# DRIVER.net
KiCad netlist of a schematic drawn in Altium Designer
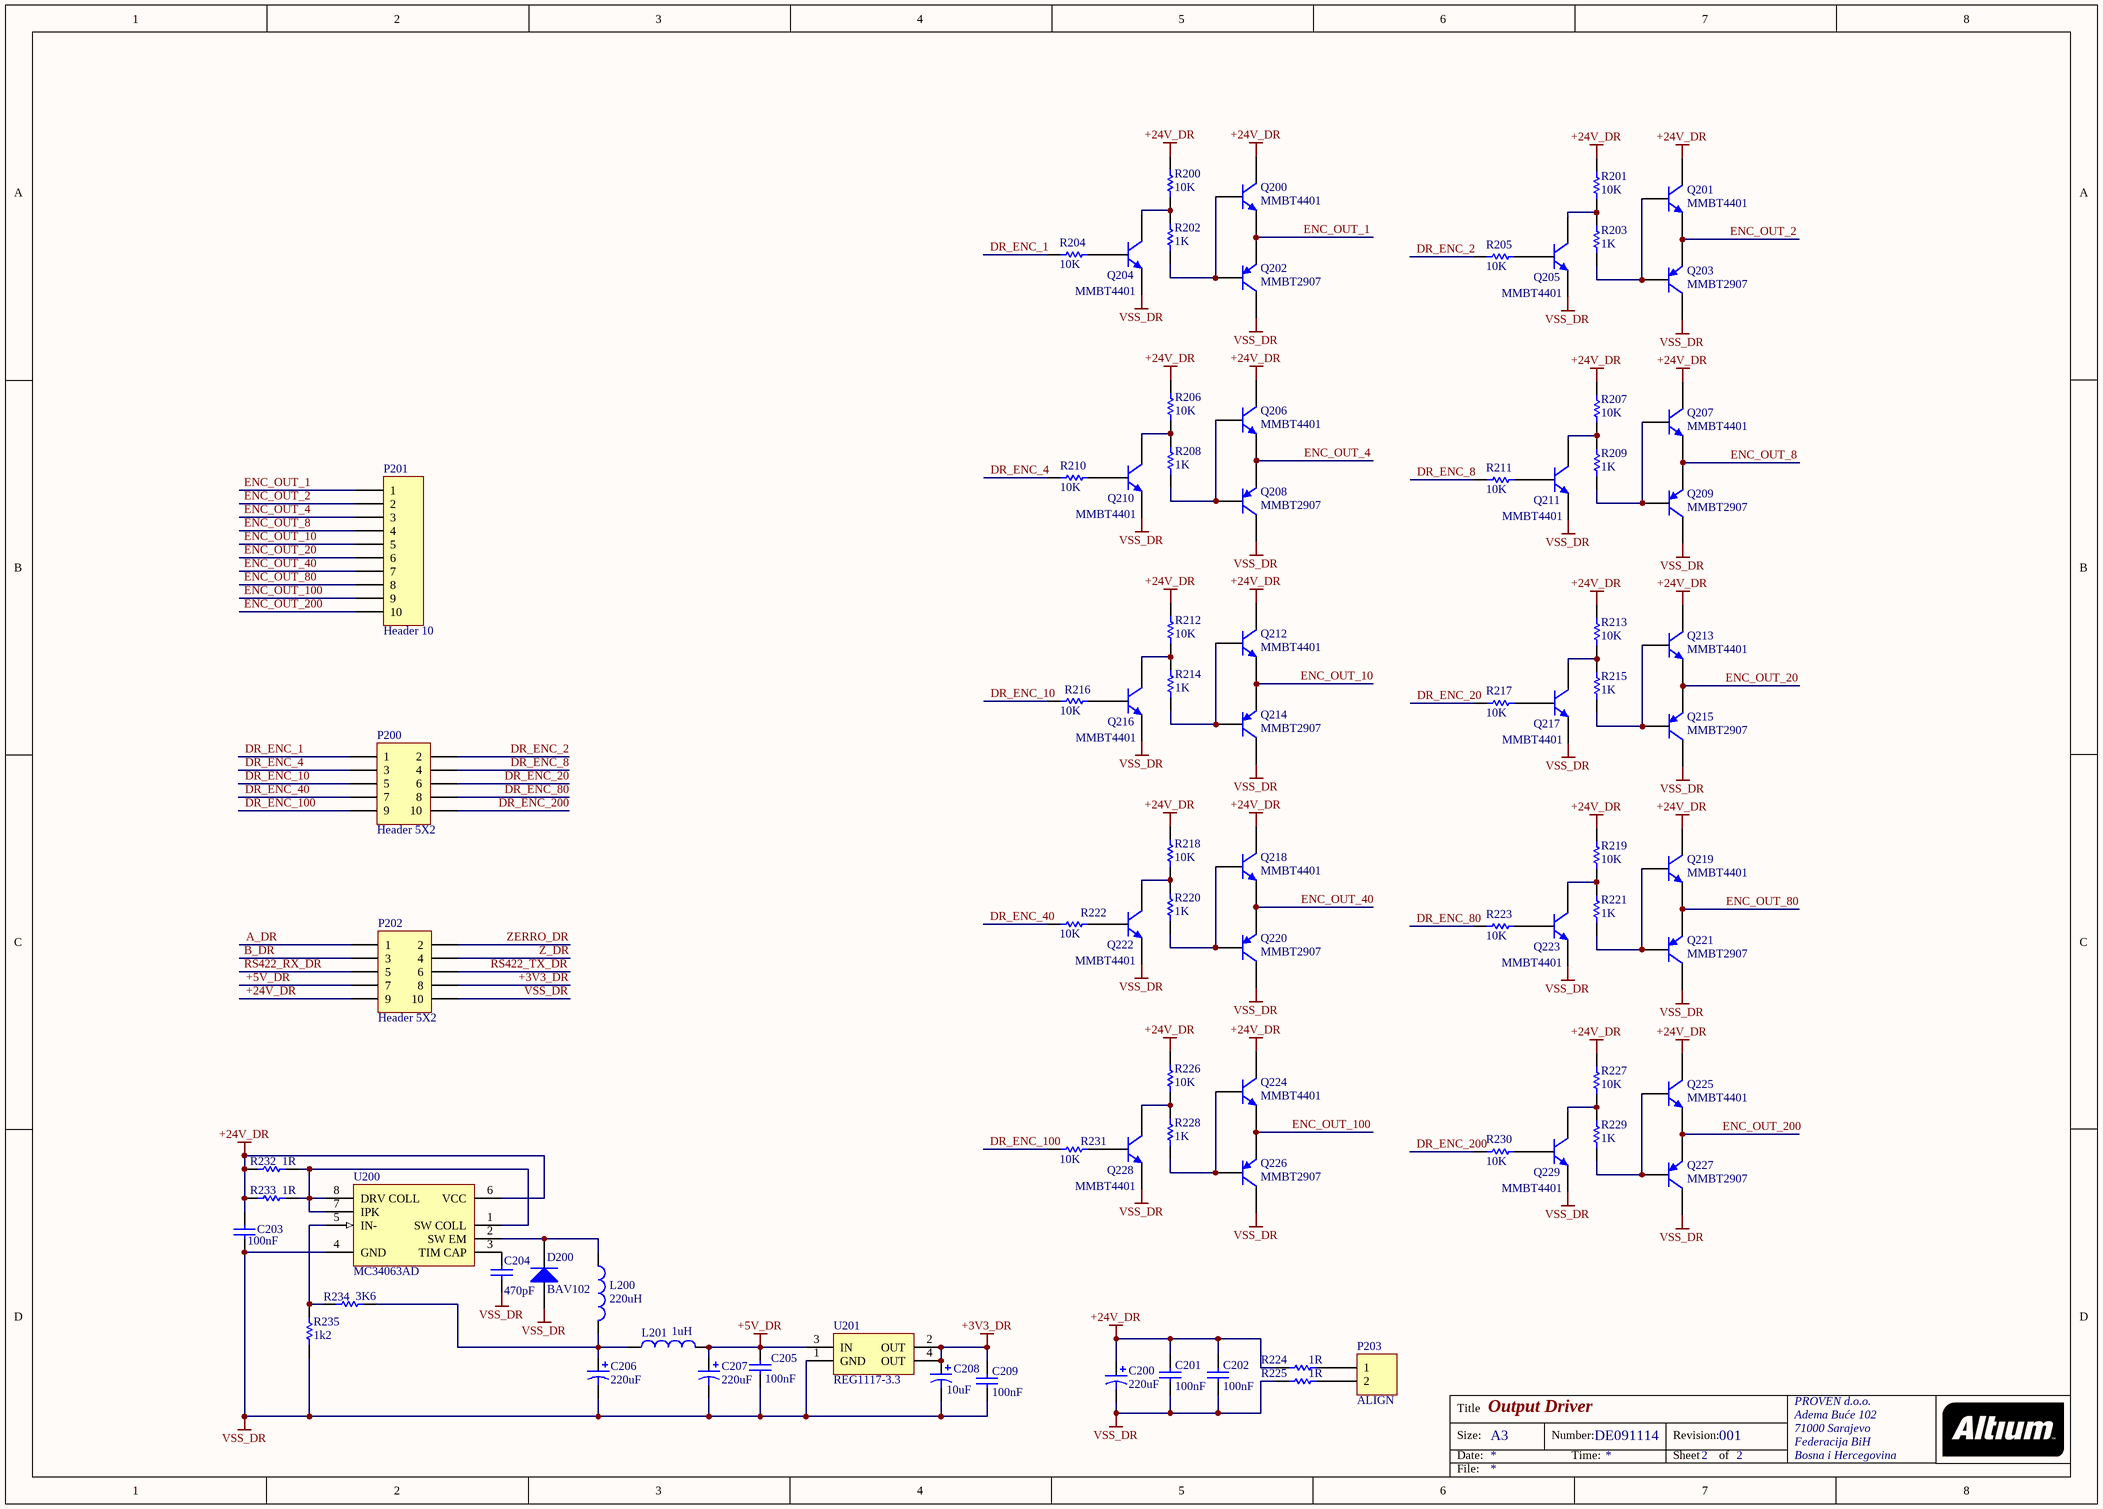
[diagram p0: DRIVER.SchDoc]

(export (version "E")
  (design (tool "Eeschema 10.0.6"))
  (components
    (comp (ref "C200")
      (value "220uF")
      (footprint "E")
      (description "Solid Aluminum Capacitor with Organic Semiconductor Electrolyte: 100uF, 20V, Bulk Pack")
      (fields (field (name "PUBLISHER") "Altium Limited"))
      (libsource (lib "Vishay Electrolytic Radial-Lead Capacitor") (part "94SS107X0020EBP"))
    )
    (comp (ref "C201")
      (value "100nF")
      (footprint "0805")
      (description "Ceramic Chip Capacitor - Standard")
      (fields (field (name "PUBLISHER") "Altium Limited"))
      (libsource (lib "KEMET Chip Capacitor") (part "C0805"))
    )
    (comp (ref "C202")
      (value "100nF")
      (footprint "0805")
      (description "Ceramic Chip Capacitor - Standard")
      (fields (field (name "PUBLISHER") "Altium Limited"))
      (libsource (lib "KEMET Chip Capacitor") (part "C0805"))
    )
    (comp (ref "C203")
      (value "100nF")
      (footprint "1206")
      (description "Ceramic Chip Capacitor - Standard")
      (fields (field (name "PUBLISHER") "Altium Limited"))
      (libsource (lib "KEMET Chip Capacitor") (part "C1206"))
    )
    (comp (ref "C204")
      (value "470pF")
      (footprint "0805")
      (description "Ceramic Chip Capacitor - Standard")
      (fields (field (name "PUBLISHER") "Altium Limited"))
      (libsource (lib "KEMET Chip Capacitor") (part "C0805"))
    )
    (comp (ref "C205")
      (value "100nF")
      (footprint "0805")
      (description "Ceramic Chip Capacitor - Standard")
      (fields (field (name "PUBLISHER") "Altium Limited"))
      (libsource (lib "KEMET Chip Capacitor") (part "C0805"))
    )
    (comp (ref "C206")
      (value "220uF")
      (footprint "CAPPR2-5X11")
      (description "Aluminum Electrolytic Capacitor, Radial Style with Long Leads: 220uF, 10V")
      (fields (field (name "PUBLISHER") "Altium Limited"))
      (libsource (lib "Vishay Roederstein Electrolytic Radial-Lead Capacitor") (part "EKA00AA322C00"))
    )
    (comp (ref "C207")
      (value "220uF")
      (footprint "CAPPR2-5X11")
      (description "Aluminum Electrolytic Capacitor, Radial Style with Long Leads: 220uF, 10V")
      (fields (field (name "PUBLISHER") "Altium Limited"))
      (libsource (lib "Vishay Roederstein Electrolytic Radial-Lead Capacitor") (part "EKA00AA322C00"))
    )
    (comp (ref "C208")
      (value "10uF")
      (footprint "49BC-C")
      (fields (field (name "PUBLISHER") "Altium Limited"))
      (libsource (lib "Vishay Sprague Tantalum Chip Capacitor") (part "49BC685B010M"))
    )
    (comp (ref "C209")
      (value "100nF")
      (footprint "0805")
      (description "Ceramic Chip Capacitor - Standard")
      (fields (field (name "PUBLISHER") "Altium Limited"))
      (libsource (lib "KEMET Chip Capacitor") (part "C0805"))
    )
    (comp (ref "D200")
      (value "BAV102")
      (footprint "SOD80C")
      (description "General-purpose Diode")
      (fields (field (name "PUBLISHER") "Altium Limited"))
      (libsource (lib "Philips Discrete Diode - Switching") (part "BAV102"))
    )
    (comp (ref "L200")
      (value "220uH")
      (footprint "Miscellaneous Devices:RB5-10.5")
      (description "SMT Power Choke Coil; Size 7.3×6.6×3.0mm, ±20% Tolerance, 0.82uH, 13A")
      (fields (field (name "PUBLISHER") "Altium Limited"))
      (libsource (lib "SSM Inductor") (part "PCMC063T-R82MN"))
    )
    (comp (ref "L201")
      (value "1uH")
      (footprint "Miscellaneous Devices:RB5-10.5")
      (description "SMT Power Choke Coil; Size 7.3×6.6×3.0mm, ±20% Tolerance, 0.82uH, 13A")
      (fields (field (name "PUBLISHER") "Altium Limited"))
      (libsource (lib "SSM Inductor") (part "PCMC063T-R82MN"))
    )
    (comp (ref "P200")
      (value "Header 5X2")
      (footprint "HDR2X5")
      (description "Header, 5-Pin, Dual row")
      (fields (field (name "PUBLISHER") "Altium Limited"))
      (libsource (lib "Miscellaneous Connectors") (part "Header 5X2"))
    )
    (comp (ref "P201")
      (value "Header 10")
      (footprint "HDR1X10")
      (description "Header, 10-Pin")
      (fields (field (name "PUBLISHER") "Altium Limited"))
      (libsource (lib "Miscellaneous Connectors") (part "Header 10"))
    )
    (comp (ref "P202")
      (value "Header 5X2")
      (footprint "HDR2X5")
      (description "Header, 5-Pin, Dual row")
      (fields (field (name "PUBLISHER") "Altium Limited"))
      (libsource (lib "Miscellaneous Connectors") (part "Header 5X2"))
    )
    (comp (ref "P203")
      (value "ALIGN")
      (footprint "HDR1X2")
      (description "Header, 2-Pin")
      (fields (field (name "PUBLISHER") "Altium Limited"))
      (libsource (lib "Miscellaneous Connectors") (part "Header 2"))
    )
    (comp (ref "Q200")
      (value "MMBT4401")
      (footprint "SOT23_N")
      (description "NPN General-purpose Transistor")
      (fields (field (name "PUBLISHER") "Altium Limited"))
      (libsource (lib "Philips Discrete BJT - Low Power") (part "BC817-16"))
    )
    (comp (ref "Q201")
      (value "MMBT4401")
      (footprint "SOT23_N")
      (description "NPN General-purpose Transistor")
      (fields (field (name "PUBLISHER") "Altium Limited"))
      (libsource (lib "Philips Discrete BJT - Low Power") (part "BC817-16"))
    )
    (comp (ref "Q202")
      (value "MMBT2907")
      (footprint "SOT23_N")
      (description "PNP General-purpose Transistor")
      (fields (field (name "PUBLISHER") "Altium Limited"))
      (libsource (lib "Philips Discrete BJT - Low Power") (part "BC807-16"))
    )
    (comp (ref "Q203")
      (value "MMBT2907")
      (footprint "SOT23_N")
      (description "PNP General-purpose Transistor")
      (fields (field (name "PUBLISHER") "Altium Limited"))
      (libsource (lib "Philips Discrete BJT - Low Power") (part "BC807-16"))
    )
    (comp (ref "Q204")
      (value "MMBT4401")
      (footprint "SOT23_N")
      (description "NPN General-purpose Transistor")
      (fields (field (name "PUBLISHER") "Altium Limited"))
      (libsource (lib "Philips Discrete BJT - Low Power") (part "BC817-16"))
    )
    (comp (ref "Q205")
      (value "MMBT4401")
      (footprint "SOT23_N")
      (description "NPN General-purpose Transistor")
      (fields (field (name "PUBLISHER") "Altium Limited"))
      (libsource (lib "Philips Discrete BJT - Low Power") (part "BC817-16"))
    )
    (comp (ref "Q206")
      (value "MMBT4401")
      (footprint "SOT23_N")
      (description "NPN General-purpose Transistor")
      (fields (field (name "PUBLISHER") "Altium Limited"))
      (libsource (lib "Philips Discrete BJT - Low Power") (part "BC817-16"))
    )
    (comp (ref "Q207")
      (value "MMBT4401")
      (footprint "SOT23_N")
      (description "NPN General-purpose Transistor")
      (fields (field (name "PUBLISHER") "Altium Limited"))
      (libsource (lib "Philips Discrete BJT - Low Power") (part "BC817-16"))
    )
    (comp (ref "Q208")
      (value "MMBT2907")
      (footprint "SOT23_N")
      (description "PNP General-purpose Transistor")
      (fields (field (name "PUBLISHER") "Altium Limited"))
      (libsource (lib "Philips Discrete BJT - Low Power") (part "BC807-16"))
    )
    (comp (ref "Q209")
      (value "MMBT2907")
      (footprint "SOT23_N")
      (description "PNP General-purpose Transistor")
      (fields (field (name "PUBLISHER") "Altium Limited"))
      (libsource (lib "Philips Discrete BJT - Low Power") (part "BC807-16"))
    )
    (comp (ref "Q210")
      (value "MMBT4401")
      (footprint "SOT23_N")
      (description "NPN General-purpose Transistor")
      (fields (field (name "PUBLISHER") "Altium Limited"))
      (libsource (lib "Philips Discrete BJT - Low Power") (part "BC817-16"))
    )
    (comp (ref "Q211")
      (value "MMBT4401")
      (footprint "SOT23_N")
      (description "NPN General-purpose Transistor")
      (fields (field (name "PUBLISHER") "Altium Limited"))
      (libsource (lib "Philips Discrete BJT - Low Power") (part "BC817-16"))
    )
    (comp (ref "Q212")
      (value "MMBT4401")
      (footprint "SOT23_N")
      (description "NPN General-purpose Transistor")
      (fields (field (name "PUBLISHER") "Altium Limited"))
      (libsource (lib "Philips Discrete BJT - Low Power") (part "BC817-16"))
    )
    (comp (ref "Q213")
      (value "MMBT4401")
      (footprint "SOT23_N")
      (description "NPN General-purpose Transistor")
      (fields (field (name "PUBLISHER") "Altium Limited"))
      (libsource (lib "Philips Discrete BJT - Low Power") (part "BC817-16"))
    )
    (comp (ref "Q214")
      (value "MMBT2907")
      (footprint "SOT23_N")
      (description "PNP General-purpose Transistor")
      (fields (field (name "PUBLISHER") "Altium Limited"))
      (libsource (lib "Philips Discrete BJT - Low Power") (part "BC807-16"))
    )
    (comp (ref "Q215")
      (value "MMBT2907")
      (footprint "SOT23_N")
      (description "PNP General-purpose Transistor")
      (fields (field (name "PUBLISHER") "Altium Limited"))
      (libsource (lib "Philips Discrete BJT - Low Power") (part "BC807-16"))
    )
    (comp (ref "Q216")
      (value "MMBT4401")
      (footprint "SOT23_N")
      (description "NPN General-purpose Transistor")
      (fields (field (name "PUBLISHER") "Altium Limited"))
      (libsource (lib "Philips Discrete BJT - Low Power") (part "BC817-16"))
    )
    (comp (ref "Q217")
      (value "MMBT4401")
      (footprint "SOT23_N")
      (description "NPN General-purpose Transistor")
      (fields (field (name "PUBLISHER") "Altium Limited"))
      (libsource (lib "Philips Discrete BJT - Low Power") (part "BC817-16"))
    )
    (comp (ref "Q218")
      (value "MMBT4401")
      (footprint "SOT23_N")
      (description "NPN General-purpose Transistor")
      (fields (field (name "PUBLISHER") "Altium Limited"))
      (libsource (lib "Philips Discrete BJT - Low Power") (part "BC817-16"))
    )
    (comp (ref "Q219")
      (value "MMBT4401")
      (footprint "SOT23_N")
      (description "NPN General-purpose Transistor")
      (fields (field (name "PUBLISHER") "Altium Limited"))
      (libsource (lib "Philips Discrete BJT - Low Power") (part "BC817-16"))
    )
    (comp (ref "Q220")
      (value "MMBT2907")
      (footprint "SOT23_N")
      (description "PNP General-purpose Transistor")
      (fields (field (name "PUBLISHER") "Altium Limited"))
      (libsource (lib "Philips Discrete BJT - Low Power") (part "BC807-16"))
    )
    (comp (ref "Q221")
      (value "MMBT2907")
      (footprint "SOT23_N")
      (description "PNP General-purpose Transistor")
      (fields (field (name "PUBLISHER") "Altium Limited"))
      (libsource (lib "Philips Discrete BJT - Low Power") (part "BC807-16"))
    )
    (comp (ref "Q222")
      (value "MMBT4401")
      (footprint "SOT23_N")
      (description "NPN General-purpose Transistor")
      (fields (field (name "PUBLISHER") "Altium Limited"))
      (libsource (lib "Philips Discrete BJT - Low Power") (part "BC817-16"))
    )
    (comp (ref "Q223")
      (value "MMBT4401")
      (footprint "SOT23_N")
      (description "NPN General-purpose Transistor")
      (fields (field (name "PUBLISHER") "Altium Limited"))
      (libsource (lib "Philips Discrete BJT - Low Power") (part "BC817-16"))
    )
    (comp (ref "Q224")
      (value "MMBT4401")
      (footprint "SOT23_N")
      (description "NPN General-purpose Transistor")
      (fields (field (name "PUBLISHER") "Altium Limited"))
      (libsource (lib "Philips Discrete BJT - Low Power") (part "BC817-16"))
    )
    (comp (ref "Q225")
      (value "MMBT4401")
      (footprint "SOT23_N")
      (description "NPN General-purpose Transistor")
      (fields (field (name "PUBLISHER") "Altium Limited"))
      (libsource (lib "Philips Discrete BJT - Low Power") (part "BC817-16"))
    )
    (comp (ref "Q226")
      (value "MMBT2907")
      (footprint "SOT23_N")
      (description "PNP General-purpose Transistor")
      (fields (field (name "PUBLISHER") "Altium Limited"))
      (libsource (lib "Philips Discrete BJT - Low Power") (part "BC807-16"))
    )
    (comp (ref "Q227")
      (value "MMBT2907")
      (footprint "SOT23_N")
      (description "PNP General-purpose Transistor")
      (fields (field (name "PUBLISHER") "Altium Limited"))
      (libsource (lib "Philips Discrete BJT - Low Power") (part "BC807-16"))
    )
    (comp (ref "Q228")
      (value "MMBT4401")
      (footprint "SOT23_N")
      (description "NPN General-purpose Transistor")
      (fields (field (name "PUBLISHER") "Altium Limited"))
      (libsource (lib "Philips Discrete BJT - Low Power") (part "BC817-16"))
    )
    (comp (ref "Q229")
      (value "MMBT4401")
      (footprint "SOT23_N")
      (description "NPN General-purpose Transistor")
      (fields (field (name "PUBLISHER") "Altium Limited"))
      (libsource (lib "Philips Discrete BJT - Low Power") (part "BC817-16"))
    )
    (comp (ref "R200")
      (value "10K")
      (footprint "ERA-0603")
      (fields (field (name "PUBLISHER") "Altium Limited"))
      (libsource (lib "Panasonic Resistor") (part "ERAV"))
    )
    (comp (ref "R201")
      (value "10K")
      (footprint "ERA-0603")
      (fields (field (name "PUBLISHER") "Altium Limited"))
      (libsource (lib "Panasonic Resistor") (part "ERAV"))
    )
    (comp (ref "R202")
      (value "1K")
      (footprint "ERA-0603")
      (fields (field (name "PUBLISHER") "Altium Limited"))
      (libsource (lib "Panasonic Resistor") (part "ERAV"))
    )
    (comp (ref "R203")
      (value "1K")
      (footprint "ERA-0603")
      (fields (field (name "PUBLISHER") "Altium Limited"))
      (libsource (lib "Panasonic Resistor") (part "ERAV"))
    )
    (comp (ref "R204")
      (value "10K")
      (footprint "ERA-0603")
      (fields (field (name "PUBLISHER") "Altium Limited"))
      (libsource (lib "Panasonic Resistor") (part "ERAV"))
    )
    (comp (ref "R205")
      (value "10K")
      (footprint "ERA-0603")
      (fields (field (name "PUBLISHER") "Altium Limited"))
      (libsource (lib "Panasonic Resistor") (part "ERAV"))
    )
    (comp (ref "R206")
      (value "10K")
      (footprint "ERA-0603")
      (fields (field (name "PUBLISHER") "Altium Limited"))
      (libsource (lib "Panasonic Resistor") (part "ERAV"))
    )
    (comp (ref "R207")
      (value "10K")
      (footprint "ERA-0603")
      (fields (field (name "PUBLISHER") "Altium Limited"))
      (libsource (lib "Panasonic Resistor") (part "ERAV"))
    )
    (comp (ref "R208")
      (value "1K")
      (footprint "ERA-0603")
      (fields (field (name "PUBLISHER") "Altium Limited"))
      (libsource (lib "Panasonic Resistor") (part "ERAV"))
    )
    (comp (ref "R209")
      (value "1K")
      (footprint "ERA-0603")
      (fields (field (name "PUBLISHER") "Altium Limited"))
      (libsource (lib "Panasonic Resistor") (part "ERAV"))
    )
    (comp (ref "R210")
      (value "10K")
      (footprint "ERA-0603")
      (fields (field (name "PUBLISHER") "Altium Limited"))
      (libsource (lib "Panasonic Resistor") (part "ERAV"))
    )
    (comp (ref "R211")
      (value "10K")
      (footprint "ERA-0603")
      (fields (field (name "PUBLISHER") "Altium Limited"))
      (libsource (lib "Panasonic Resistor") (part "ERAV"))
    )
    (comp (ref "R212")
      (value "10K")
      (footprint "ERA-0603")
      (fields (field (name "PUBLISHER") "Altium Limited"))
      (libsource (lib "Panasonic Resistor") (part "ERAV"))
    )
    (comp (ref "R213")
      (value "10K")
      (footprint "ERA-0603")
      (fields (field (name "PUBLISHER") "Altium Limited"))
      (libsource (lib "Panasonic Resistor") (part "ERAV"))
    )
    (comp (ref "R214")
      (value "1K")
      (footprint "ERA-0603")
      (fields (field (name "PUBLISHER") "Altium Limited"))
      (libsource (lib "Panasonic Resistor") (part "ERAV"))
    )
    (comp (ref "R215")
      (value "1K")
      (footprint "ERA-0603")
      (fields (field (name "PUBLISHER") "Altium Limited"))
      (libsource (lib "Panasonic Resistor") (part "ERAV"))
    )
    (comp (ref "R216")
      (value "10K")
      (footprint "ERA-0603")
      (fields (field (name "PUBLISHER") "Altium Limited"))
      (libsource (lib "Panasonic Resistor") (part "ERAV"))
    )
    (comp (ref "R217")
      (value "10K")
      (footprint "ERA-0603")
      (fields (field (name "PUBLISHER") "Altium Limited"))
      (libsource (lib "Panasonic Resistor") (part "ERAV"))
    )
    (comp (ref "R218")
      (value "10K")
      (footprint "ERA-0603")
      (fields (field (name "PUBLISHER") "Altium Limited"))
      (libsource (lib "Panasonic Resistor") (part "ERAV"))
    )
    (comp (ref "R219")
      (value "10K")
      (footprint "ERA-0603")
      (fields (field (name "PUBLISHER") "Altium Limited"))
      (libsource (lib "Panasonic Resistor") (part "ERAV"))
    )
    (comp (ref "R220")
      (value "1K")
      (footprint "ERA-0603")
      (fields (field (name "PUBLISHER") "Altium Limited"))
      (libsource (lib "Panasonic Resistor") (part "ERAV"))
    )
    (comp (ref "R221")
      (value "1K")
      (footprint "ERA-0603")
      (fields (field (name "PUBLISHER") "Altium Limited"))
      (libsource (lib "Panasonic Resistor") (part "ERAV"))
    )
    (comp (ref "R222")
      (value "10K")
      (footprint "ERA-0603")
      (fields (field (name "PUBLISHER") "Altium Limited"))
      (libsource (lib "Panasonic Resistor") (part "ERAV"))
    )
    (comp (ref "R223")
      (value "10K")
      (footprint "ERA-0603")
      (fields (field (name "PUBLISHER") "Altium Limited"))
      (libsource (lib "Panasonic Resistor") (part "ERAV"))
    )
    (comp (ref "R224")
      (value "1R")
      (footprint "ERA-0603")
      (fields (field (name "PUBLISHER") "Altium Limited"))
      (libsource (lib "Panasonic Resistor") (part "ERAV"))
    )
    (comp (ref "R225")
      (value "1R")
      (footprint "ERA-0603")
      (fields (field (name "PUBLISHER") "Altium Limited"))
      (libsource (lib "Panasonic Resistor") (part "ERAV"))
    )
    (comp (ref "R226")
      (value "10K")
      (footprint "ERA-0603")
      (fields (field (name "PUBLISHER") "Altium Limited"))
      (libsource (lib "Panasonic Resistor") (part "ERAV"))
    )
    (comp (ref "R227")
      (value "10K")
      (footprint "ERA-0603")
      (fields (field (name "PUBLISHER") "Altium Limited"))
      (libsource (lib "Panasonic Resistor") (part "ERAV"))
    )
    (comp (ref "R228")
      (value "1K")
      (footprint "ERA-0603")
      (fields (field (name "PUBLISHER") "Altium Limited"))
      (libsource (lib "Panasonic Resistor") (part "ERAV"))
    )
    (comp (ref "R229")
      (value "1K")
      (footprint "ERA-0603")
      (fields (field (name "PUBLISHER") "Altium Limited"))
      (libsource (lib "Panasonic Resistor") (part "ERAV"))
    )
    (comp (ref "R230")
      (value "10K")
      (footprint "ERA-0603")
      (fields (field (name "PUBLISHER") "Altium Limited"))
      (libsource (lib "Panasonic Resistor") (part "ERAV"))
    )
    (comp (ref "R231")
      (value "10K")
      (footprint "ERA-0603")
      (fields (field (name "PUBLISHER") "Altium Limited"))
      (libsource (lib "Panasonic Resistor") (part "ERAV"))
    )
    (comp (ref "R232")
      (value "1R")
      (footprint "ERA-0805")
      (fields (field (name "PUBLISHER") "Altium Limited"))
      (libsource (lib "Panasonic Resistor") (part "ERAS"))
    )
    (comp (ref "R233")
      (value "1R")
      (footprint "ERA-0805")
      (fields (field (name "PUBLISHER") "Altium Limited"))
      (libsource (lib "Panasonic Resistor") (part "ERAS"))
    )
    (comp (ref "R234")
      (value "3K6")
      (footprint "ERA-0805")
      (fields (field (name "PUBLISHER") "Altium Limited"))
      (libsource (lib "Panasonic Resistor") (part "ERAS"))
    )
    (comp (ref "R235")
      (value "1k2")
      (footprint "ERA-0805")
      (fields (field (name "PUBLISHER") "Altium Limited"))
      (libsource (lib "Panasonic Resistor") (part "ERAS"))
    )
    (comp (ref "U200")
      (value "MC34063AD")
      (footprint "751-05_N")
      (description "DC-to-DC Converter Control Circuit")
      (fields (field (name "PUBLISHER") "Altium Limited"))
      (libsource (lib "ON Semi Power Mgt DC-DC Converter") (part "MC34063AD"))
    )
    (comp (ref "U201")
      (value "REG1117-3.3")
      (footprint "ZZ311")
      (description "800mA and 1A Low Dropout Positive Regulator 2.85V, 3.3V, 5V, and Adjustable")
      (fields (field (name "PUBLISHER") "Altium Limited"))
      (libsource (lib "BB Power Mgt Voltage Regulator") (part "REG1117-3.3"))
    )
  )
  (nets
    (net (code "1") (name "+3V3_DR") (class "Default")
      (node (ref "C208") (pin "1") (pinfunction "1_1") (pintype "passive"))
      (node (ref "C209") (pin "2") (pinfunction "2_2") (pintype "passive"))
      (node (ref "P202") (pin "8") (pinfunction "8_8") (pintype "passive"))
      (node (ref "U201") (pin "2") (pinfunction "OUT_2") (pintype "power_in"))
      (node (ref "U201") (pin "4") (pinfunction "OUT_4") (pintype "power_in"))
    )
    (net (code "2") (name "+5V_DR") (class "Default")
      (node (ref "C205") (pin "2") (pinfunction "2_2") (pintype "passive"))
      (node (ref "C207") (pin "1") (pinfunction "1_1") (pintype "passive"))
      (node (ref "L201") (pin "2") (pinfunction "2_2") (pintype "passive"))
      (node (ref "P202") (pin "7") (pinfunction "7_7") (pintype "passive"))
      (node (ref "U201") (pin "3") (pinfunction "IN_3") (pintype "power_in"))
    )
    (net (code "3") (name "+24V_DR") (class "Default")
      (node (ref "C200") (pin "1") (pinfunction "1_1") (pintype "passive"))
      (node (ref "C201") (pin "2") (pinfunction "2_2") (pintype "passive"))
      (node (ref "C202") (pin "2") (pinfunction "2_2") (pintype "passive"))
      (node (ref "C203") (pin "2") (pinfunction "2_2") (pintype "passive"))
      (node (ref "P202") (pin "9") (pinfunction "9_9") (pintype "passive"))
      (node (ref "Q200") (pin "3") (pinfunction "C_3") (pintype "passive"))
      (node (ref "Q201") (pin "3") (pinfunction "C_3") (pintype "passive"))
      (node (ref "Q206") (pin "3") (pinfunction "C_3") (pintype "passive"))
      (node (ref "Q207") (pin "3") (pinfunction "C_3") (pintype "passive"))
      (node (ref "Q212") (pin "3") (pinfunction "C_3") (pintype "passive"))
      (node (ref "Q213") (pin "3") (pinfunction "C_3") (pintype "passive"))
      (node (ref "Q218") (pin "3") (pinfunction "C_3") (pintype "passive"))
      (node (ref "Q219") (pin "3") (pinfunction "C_3") (pintype "passive"))
      (node (ref "Q224") (pin "3") (pinfunction "C_3") (pintype "passive"))
      (node (ref "Q225") (pin "3") (pinfunction "C_3") (pintype "passive"))
      (node (ref "R200") (pin "1") (pinfunction "1_1") (pintype "passive"))
      (node (ref "R201") (pin "1") (pinfunction "1_1") (pintype "passive"))
      (node (ref "R206") (pin "1") (pinfunction "1_1") (pintype "passive"))
      (node (ref "R207") (pin "1") (pinfunction "1_1") (pintype "passive"))
      (node (ref "R212") (pin "1") (pinfunction "1_1") (pintype "passive"))
      (node (ref "R213") (pin "1") (pinfunction "1_1") (pintype "passive"))
      (node (ref "R218") (pin "1") (pinfunction "1_1") (pintype "passive"))
      (node (ref "R219") (pin "1") (pinfunction "1_1") (pintype "passive"))
      (node (ref "R224") (pin "1") (pinfunction "1_1") (pintype "passive"))
      (node (ref "R226") (pin "1") (pinfunction "1_1") (pintype "passive"))
      (node (ref "R227") (pin "1") (pinfunction "1_1") (pintype "passive"))
      (node (ref "R232") (pin "1") (pinfunction "1_1") (pintype "passive"))
      (node (ref "R233") (pin "1") (pinfunction "1_1") (pintype "passive"))
      (node (ref "U200") (pin "6") (pinfunction "VCC_6") (pintype "power_in"))
    )
    (net (code "4") (name "/A_DR") (class "Default")
      (node (ref "P202") (pin "1") (pinfunction "1_1") (pintype "passive"))
    )
    (net (code "5") (name "/B_DR") (class "Default")
      (node (ref "P202") (pin "3") (pinfunction "3_3") (pintype "passive"))
    )
    (net (code "6") (name "/DR_ENC_1") (class "Default")
      (node (ref "P200") (pin "1") (pinfunction "1_1") (pintype "passive"))
      (node (ref "R204") (pin "2") (pinfunction "2_2") (pintype "passive"))
    )
    (net (code "7") (name "/DR_ENC_2") (class "Default")
      (node (ref "P200") (pin "2") (pinfunction "2_2") (pintype "passive"))
      (node (ref "R205") (pin "2") (pinfunction "2_2") (pintype "passive"))
    )
    (net (code "8") (name "/DR_ENC_4") (class "Default")
      (node (ref "P200") (pin "3") (pinfunction "3_3") (pintype "passive"))
      (node (ref "R210") (pin "2") (pinfunction "2_2") (pintype "passive"))
    )
    (net (code "9") (name "/DR_ENC_8") (class "Default")
      (node (ref "P200") (pin "4") (pinfunction "4_4") (pintype "passive"))
      (node (ref "R211") (pin "2") (pinfunction "2_2") (pintype "passive"))
    )
    (net (code "10") (name "/DR_ENC_10") (class "Default")
      (node (ref "P200") (pin "5") (pinfunction "5_5") (pintype "passive"))
      (node (ref "R216") (pin "2") (pinfunction "2_2") (pintype "passive"))
    )
    (net (code "11") (name "/DR_ENC_20") (class "Default")
      (node (ref "P200") (pin "6") (pinfunction "6_6") (pintype "passive"))
      (node (ref "R217") (pin "2") (pinfunction "2_2") (pintype "passive"))
    )
    (net (code "12") (name "/DR_ENC_40") (class "Default")
      (node (ref "P200") (pin "7") (pinfunction "7_7") (pintype "passive"))
      (node (ref "R222") (pin "2") (pinfunction "2_2") (pintype "passive"))
    )
    (net (code "13") (name "/DR_ENC_80") (class "Default")
      (node (ref "P200") (pin "8") (pinfunction "8_8") (pintype "passive"))
      (node (ref "R223") (pin "2") (pinfunction "2_2") (pintype "passive"))
    )
    (net (code "14") (name "/DR_ENC_100") (class "Default")
      (node (ref "P200") (pin "9") (pinfunction "9_9") (pintype "passive"))
      (node (ref "R231") (pin "2") (pinfunction "2_2") (pintype "passive"))
    )
    (net (code "15") (name "/DR_ENC_200") (class "Default")
      (node (ref "P200") (pin "10") (pinfunction "10_10") (pintype "passive"))
      (node (ref "R230") (pin "2") (pinfunction "2_2") (pintype "passive"))
    )
    (net (code "16") (name "/ENC_OUT_1") (class "Default")
      (node (ref "P201") (pin "1") (pinfunction "1_1") (pintype "passive"))
      (node (ref "Q200") (pin "2") (pinfunction "E_2") (pintype "passive"))
      (node (ref "Q202") (pin "2") (pinfunction "E_2") (pintype "passive"))
    )
    (net (code "17") (name "/ENC_OUT_2") (class "Default")
      (node (ref "P201") (pin "2") (pinfunction "2_2") (pintype "passive"))
      (node (ref "Q201") (pin "2") (pinfunction "E_2") (pintype "passive"))
      (node (ref "Q203") (pin "2") (pinfunction "E_2") (pintype "passive"))
    )
    (net (code "18") (name "/ENC_OUT_4") (class "Default")
      (node (ref "P201") (pin "3") (pinfunction "3_3") (pintype "passive"))
      (node (ref "Q206") (pin "2") (pinfunction "E_2") (pintype "passive"))
      (node (ref "Q208") (pin "2") (pinfunction "E_2") (pintype "passive"))
    )
    (net (code "19") (name "/ENC_OUT_8") (class "Default")
      (node (ref "P201") (pin "4") (pinfunction "4_4") (pintype "passive"))
      (node (ref "Q207") (pin "2") (pinfunction "E_2") (pintype "passive"))
      (node (ref "Q209") (pin "2") (pinfunction "E_2") (pintype "passive"))
    )
    (net (code "20") (name "/ENC_OUT_10") (class "Default")
      (node (ref "P201") (pin "5") (pinfunction "5_5") (pintype "passive"))
      (node (ref "Q212") (pin "2") (pinfunction "E_2") (pintype "passive"))
      (node (ref "Q214") (pin "2") (pinfunction "E_2") (pintype "passive"))
    )
    (net (code "21") (name "/ENC_OUT_20") (class "Default")
      (node (ref "P201") (pin "6") (pinfunction "6_6") (pintype "passive"))
      (node (ref "Q213") (pin "2") (pinfunction "E_2") (pintype "passive"))
      (node (ref "Q215") (pin "2") (pinfunction "E_2") (pintype "passive"))
    )
    (net (code "22") (name "/ENC_OUT_40") (class "Default")
      (node (ref "P201") (pin "7") (pinfunction "7_7") (pintype "passive"))
      (node (ref "Q218") (pin "2") (pinfunction "E_2") (pintype "passive"))
      (node (ref "Q220") (pin "2") (pinfunction "E_2") (pintype "passive"))
    )
    (net (code "23") (name "/ENC_OUT_80") (class "Default")
      (node (ref "P201") (pin "8") (pinfunction "8_8") (pintype "passive"))
      (node (ref "Q219") (pin "2") (pinfunction "E_2") (pintype "passive"))
      (node (ref "Q221") (pin "2") (pinfunction "E_2") (pintype "passive"))
    )
    (net (code "24") (name "/ENC_OUT_100") (class "Default")
      (node (ref "P201") (pin "9") (pinfunction "9_9") (pintype "passive"))
      (node (ref "Q224") (pin "2") (pinfunction "E_2") (pintype "passive"))
      (node (ref "Q226") (pin "2") (pinfunction "E_2") (pintype "passive"))
    )
    (net (code "25") (name "/ENC_OUT_200") (class "Default")
      (node (ref "P201") (pin "10") (pinfunction "10_10") (pintype "passive"))
      (node (ref "Q225") (pin "2") (pinfunction "E_2") (pintype "passive"))
      (node (ref "Q227") (pin "2") (pinfunction "E_2") (pintype "passive"))
    )
    (net (code "26") (name "/RS422_RX_DR") (class "Default")
      (node (ref "P202") (pin "5") (pinfunction "5_5") (pintype "passive"))
    )
    (net (code "27") (name "/RS422_TX_DR") (class "Default")
      (node (ref "P202") (pin "6") (pinfunction "6_6") (pintype "passive"))
    )
    (net (code "28") (name "/ZERRO_DR") (class "Default")
      (node (ref "P202") (pin "2") (pinfunction "2_2") (pintype "passive"))
    )
    (net (code "29") (name "/Z_DR") (class "Default")
      (node (ref "P202") (pin "4") (pinfunction "4_4") (pintype "passive"))
    )
    (net (code "30") (name "Net-(C206-Pad1)") (class "Default")
      (node (ref "C206") (pin "1") (pinfunction "1_1") (pintype "passive"))
      (node (ref "L200") (pin "2") (pinfunction "2_2") (pintype "passive"))
      (node (ref "L201") (pin "1") (pinfunction "1_1") (pintype "passive"))
      (node (ref "R234") (pin "2") (pinfunction "2_2") (pintype "passive"))
    )
    (net (code "31") (name "Net-(D200-K)") (class "Default")
      (node (ref "D200") (pin "2") (pinfunction "K_2") (pintype "passive"))
      (node (ref "L200") (pin "1") (pinfunction "1_1") (pintype "passive"))
      (node (ref "U200") (pin "2") (pinfunction "SW_EM_2") (pintype "passive"))
    )
    (net (code "32") (name "Net-(P203-Pad1)") (class "Default")
      (node (ref "P203") (pin "1") (pinfunction "1_1") (pintype "passive"))
      (node (ref "R224") (pin "2") (pinfunction "2_2") (pintype "passive"))
    )
    (net (code "33") (name "Net-(P203-Pad2)") (class "Default")
      (node (ref "P203") (pin "2") (pinfunction "2_2") (pintype "passive"))
      (node (ref "R225") (pin "2") (pinfunction "2_2") (pintype "passive"))
    )
    (net (code "34") (name "Net-(Q200-B)") (class "Default")
      (node (ref "Q200") (pin "1") (pinfunction "B_1") (pintype "passive"))
      (node (ref "Q202") (pin "1") (pinfunction "B_1") (pintype "passive"))
      (node (ref "R202") (pin "1") (pinfunction "1_1") (pintype "passive"))
    )
    (net (code "35") (name "Net-(Q201-B)") (class "Default")
      (node (ref "Q201") (pin "1") (pinfunction "B_1") (pintype "passive"))
      (node (ref "Q203") (pin "1") (pinfunction "B_1") (pintype "passive"))
      (node (ref "R203") (pin "1") (pinfunction "1_1") (pintype "passive"))
    )
    (net (code "36") (name "Net-(Q204-B)") (class "Default")
      (node (ref "Q204") (pin "1") (pinfunction "B_1") (pintype "passive"))
      (node (ref "R204") (pin "1") (pinfunction "1_1") (pintype "passive"))
    )
    (net (code "37") (name "Net-(Q204-C)") (class "Default")
      (node (ref "Q204") (pin "3") (pinfunction "C_3") (pintype "passive"))
      (node (ref "R200") (pin "2") (pinfunction "2_2") (pintype "passive"))
      (node (ref "R202") (pin "2") (pinfunction "2_2") (pintype "passive"))
    )
    (net (code "38") (name "Net-(Q205-B)") (class "Default")
      (node (ref "Q205") (pin "1") (pinfunction "B_1") (pintype "passive"))
      (node (ref "R205") (pin "1") (pinfunction "1_1") (pintype "passive"))
    )
    (net (code "39") (name "Net-(Q205-C)") (class "Default")
      (node (ref "Q205") (pin "3") (pinfunction "C_3") (pintype "passive"))
      (node (ref "R201") (pin "2") (pinfunction "2_2") (pintype "passive"))
      (node (ref "R203") (pin "2") (pinfunction "2_2") (pintype "passive"))
    )
    (net (code "40") (name "Net-(Q206-B)") (class "Default")
      (node (ref "Q206") (pin "1") (pinfunction "B_1") (pintype "passive"))
      (node (ref "Q208") (pin "1") (pinfunction "B_1") (pintype "passive"))
      (node (ref "R208") (pin "1") (pinfunction "1_1") (pintype "passive"))
    )
    (net (code "41") (name "Net-(Q207-B)") (class "Default")
      (node (ref "Q207") (pin "1") (pinfunction "B_1") (pintype "passive"))
      (node (ref "Q209") (pin "1") (pinfunction "B_1") (pintype "passive"))
      (node (ref "R209") (pin "1") (pinfunction "1_1") (pintype "passive"))
    )
    (net (code "42") (name "Net-(Q210-B)") (class "Default")
      (node (ref "Q210") (pin "1") (pinfunction "B_1") (pintype "passive"))
      (node (ref "R210") (pin "1") (pinfunction "1_1") (pintype "passive"))
    )
    (net (code "43") (name "Net-(Q210-C)") (class "Default")
      (node (ref "Q210") (pin "3") (pinfunction "C_3") (pintype "passive"))
      (node (ref "R206") (pin "2") (pinfunction "2_2") (pintype "passive"))
      (node (ref "R208") (pin "2") (pinfunction "2_2") (pintype "passive"))
    )
    (net (code "44") (name "Net-(Q211-B)") (class "Default")
      (node (ref "Q211") (pin "1") (pinfunction "B_1") (pintype "passive"))
      (node (ref "R211") (pin "1") (pinfunction "1_1") (pintype "passive"))
    )
    (net (code "45") (name "Net-(Q211-C)") (class "Default")
      (node (ref "Q211") (pin "3") (pinfunction "C_3") (pintype "passive"))
      (node (ref "R207") (pin "2") (pinfunction "2_2") (pintype "passive"))
      (node (ref "R209") (pin "2") (pinfunction "2_2") (pintype "passive"))
    )
    (net (code "46") (name "Net-(Q212-B)") (class "Default")
      (node (ref "Q212") (pin "1") (pinfunction "B_1") (pintype "passive"))
      (node (ref "Q214") (pin "1") (pinfunction "B_1") (pintype "passive"))
      (node (ref "R214") (pin "1") (pinfunction "1_1") (pintype "passive"))
    )
    (net (code "47") (name "Net-(Q213-B)") (class "Default")
      (node (ref "Q213") (pin "1") (pinfunction "B_1") (pintype "passive"))
      (node (ref "Q215") (pin "1") (pinfunction "B_1") (pintype "passive"))
      (node (ref "R215") (pin "1") (pinfunction "1_1") (pintype "passive"))
    )
    (net (code "48") (name "Net-(Q216-B)") (class "Default")
      (node (ref "Q216") (pin "1") (pinfunction "B_1") (pintype "passive"))
      (node (ref "R216") (pin "1") (pinfunction "1_1") (pintype "passive"))
    )
    (net (code "49") (name "Net-(Q216-C)") (class "Default")
      (node (ref "Q216") (pin "3") (pinfunction "C_3") (pintype "passive"))
      (node (ref "R212") (pin "2") (pinfunction "2_2") (pintype "passive"))
      (node (ref "R214") (pin "2") (pinfunction "2_2") (pintype "passive"))
    )
    (net (code "50") (name "Net-(Q217-B)") (class "Default")
      (node (ref "Q217") (pin "1") (pinfunction "B_1") (pintype "passive"))
      (node (ref "R217") (pin "1") (pinfunction "1_1") (pintype "passive"))
    )
    (net (code "51") (name "Net-(Q217-C)") (class "Default")
      (node (ref "Q217") (pin "3") (pinfunction "C_3") (pintype "passive"))
      (node (ref "R213") (pin "2") (pinfunction "2_2") (pintype "passive"))
      (node (ref "R215") (pin "2") (pinfunction "2_2") (pintype "passive"))
    )
    (net (code "52") (name "Net-(Q218-B)") (class "Default")
      (node (ref "Q218") (pin "1") (pinfunction "B_1") (pintype "passive"))
      (node (ref "Q220") (pin "1") (pinfunction "B_1") (pintype "passive"))
      (node (ref "R220") (pin "1") (pinfunction "1_1") (pintype "passive"))
    )
    (net (code "53") (name "Net-(Q219-B)") (class "Default")
      (node (ref "Q219") (pin "1") (pinfunction "B_1") (pintype "passive"))
      (node (ref "Q221") (pin "1") (pinfunction "B_1") (pintype "passive"))
      (node (ref "R221") (pin "1") (pinfunction "1_1") (pintype "passive"))
    )
    (net (code "54") (name "Net-(Q222-B)") (class "Default")
      (node (ref "Q222") (pin "1") (pinfunction "B_1") (pintype "passive"))
      (node (ref "R222") (pin "1") (pinfunction "1_1") (pintype "passive"))
    )
    (net (code "55") (name "Net-(Q222-C)") (class "Default")
      (node (ref "Q222") (pin "3") (pinfunction "C_3") (pintype "passive"))
      (node (ref "R218") (pin "2") (pinfunction "2_2") (pintype "passive"))
      (node (ref "R220") (pin "2") (pinfunction "2_2") (pintype "passive"))
    )
    (net (code "56") (name "Net-(Q223-B)") (class "Default")
      (node (ref "Q223") (pin "1") (pinfunction "B_1") (pintype "passive"))
      (node (ref "R223") (pin "1") (pinfunction "1_1") (pintype "passive"))
    )
    (net (code "57") (name "Net-(Q223-C)") (class "Default")
      (node (ref "Q223") (pin "3") (pinfunction "C_3") (pintype "passive"))
      (node (ref "R219") (pin "2") (pinfunction "2_2") (pintype "passive"))
      (node (ref "R221") (pin "2") (pinfunction "2_2") (pintype "passive"))
    )
    (net (code "58") (name "Net-(Q224-B)") (class "Default")
      (node (ref "Q224") (pin "1") (pinfunction "B_1") (pintype "passive"))
      (node (ref "Q226") (pin "1") (pinfunction "B_1") (pintype "passive"))
      (node (ref "R228") (pin "1") (pinfunction "1_1") (pintype "passive"))
    )
    (net (code "59") (name "Net-(Q225-B)") (class "Default")
      (node (ref "Q225") (pin "1") (pinfunction "B_1") (pintype "passive"))
      (node (ref "Q227") (pin "1") (pinfunction "B_1") (pintype "passive"))
      (node (ref "R229") (pin "1") (pinfunction "1_1") (pintype "passive"))
    )
    (net (code "60") (name "Net-(Q228-B)") (class "Default")
      (node (ref "Q228") (pin "1") (pinfunction "B_1") (pintype "passive"))
      (node (ref "R231") (pin "1") (pinfunction "1_1") (pintype "passive"))
    )
    (net (code "61") (name "Net-(Q228-C)") (class "Default")
      (node (ref "Q228") (pin "3") (pinfunction "C_3") (pintype "passive"))
      (node (ref "R226") (pin "2") (pinfunction "2_2") (pintype "passive"))
      (node (ref "R228") (pin "2") (pinfunction "2_2") (pintype "passive"))
    )
    (net (code "62") (name "Net-(Q229-B)") (class "Default")
      (node (ref "Q229") (pin "1") (pinfunction "B_1") (pintype "passive"))
      (node (ref "R230") (pin "1") (pinfunction "1_1") (pintype "passive"))
    )
    (net (code "63") (name "Net-(Q229-C)") (class "Default")
      (node (ref "Q229") (pin "3") (pinfunction "C_3") (pintype "passive"))
      (node (ref "R227") (pin "2") (pinfunction "2_2") (pintype "passive"))
      (node (ref "R229") (pin "2") (pinfunction "2_2") (pintype "passive"))
    )
    (net (code "64") (name "Net-(U200-DRV_COLL)") (class "Default")
      (node (ref "R232") (pin "2") (pinfunction "2_2") (pintype "passive"))
      (node (ref "R233") (pin "2") (pinfunction "2_2") (pintype "passive"))
      (node (ref "U200") (pin "1") (pinfunction "SW_COLL_1") (pintype "passive"))
      (node (ref "U200") (pin "7") (pinfunction "IPK_7") (pintype "passive"))
      (node (ref "U200") (pin "8") (pinfunction "DRV_COLL_8") (pintype "open_collector"))
    )
    (net (code "65") (name "Net-(U200-IN-)") (class "Default")
      (node (ref "R234") (pin "1") (pinfunction "1_1") (pintype "passive"))
      (node (ref "R235") (pin "2") (pinfunction "2_2") (pintype "passive"))
      (node (ref "U200") (pin "5") (pinfunction "IN-_5") (pintype "input"))
    )
    (net (code "66") (name "Net-(U200-TIM_CAP)") (class "Default")
      (node (ref "C204") (pin "2") (pinfunction "2_2") (pintype "passive"))
      (node (ref "U200") (pin "3") (pinfunction "TIM_CAP_3") (pintype "passive"))
    )
    (net (code "67") (name "VSS_DR") (class "Default")
      (node (ref "C200") (pin "2") (pinfunction "2_2") (pintype "passive"))
      (node (ref "C201") (pin "1") (pinfunction "1_1") (pintype "passive"))
      (node (ref "C202") (pin "1") (pinfunction "1_1") (pintype "passive"))
      (node (ref "C203") (pin "1") (pinfunction "1_1") (pintype "passive"))
      (node (ref "C204") (pin "1") (pinfunction "1_1") (pintype "passive"))
      (node (ref "C205") (pin "1") (pinfunction "1_1") (pintype "passive"))
      (node (ref "C206") (pin "2") (pinfunction "2_2") (pintype "passive"))
      (node (ref "C207") (pin "2") (pinfunction "2_2") (pintype "passive"))
      (node (ref "C208") (pin "2") (pinfunction "2_2") (pintype "passive"))
      (node (ref "C209") (pin "1") (pinfunction "1_1") (pintype "passive"))
      (node (ref "D200") (pin "1") (pinfunction "A_1") (pintype "passive"))
      (node (ref "P202") (pin "10") (pinfunction "10_10") (pintype "passive"))
      (node (ref "Q202") (pin "3") (pinfunction "C_3") (pintype "passive"))
      (node (ref "Q203") (pin "3") (pinfunction "C_3") (pintype "passive"))
      (node (ref "Q204") (pin "2") (pinfunction "E_2") (pintype "passive"))
      (node (ref "Q205") (pin "2") (pinfunction "E_2") (pintype "passive"))
      (node (ref "Q208") (pin "3") (pinfunction "C_3") (pintype "passive"))
      (node (ref "Q209") (pin "3") (pinfunction "C_3") (pintype "passive"))
      (node (ref "Q210") (pin "2") (pinfunction "E_2") (pintype "passive"))
      (node (ref "Q211") (pin "2") (pinfunction "E_2") (pintype "passive"))
      (node (ref "Q214") (pin "3") (pinfunction "C_3") (pintype "passive"))
      (node (ref "Q215") (pin "3") (pinfunction "C_3") (pintype "passive"))
      (node (ref "Q216") (pin "2") (pinfunction "E_2") (pintype "passive"))
      (node (ref "Q217") (pin "2") (pinfunction "E_2") (pintype "passive"))
      (node (ref "Q220") (pin "3") (pinfunction "C_3") (pintype "passive"))
      (node (ref "Q221") (pin "3") (pinfunction "C_3") (pintype "passive"))
      (node (ref "Q222") (pin "2") (pinfunction "E_2") (pintype "passive"))
      (node (ref "Q223") (pin "2") (pinfunction "E_2") (pintype "passive"))
      (node (ref "Q226") (pin "3") (pinfunction "C_3") (pintype "passive"))
      (node (ref "Q227") (pin "3") (pinfunction "C_3") (pintype "passive"))
      (node (ref "Q228") (pin "2") (pinfunction "E_2") (pintype "passive"))
      (node (ref "Q229") (pin "2") (pinfunction "E_2") (pintype "passive"))
      (node (ref "R225") (pin "1") (pinfunction "1_1") (pintype "passive"))
      (node (ref "R235") (pin "1") (pinfunction "1_1") (pintype "passive"))
      (node (ref "U200") (pin "4") (pinfunction "GND_4") (pintype "power_in"))
      (node (ref "U201") (pin "1") (pinfunction "GND_1") (pintype "power_in"))
    )
  )
)
